# ProDoc_Rev1_21_2024-06-05.net
KiCad netlist of a schematic drawn in EasyEDA Pro
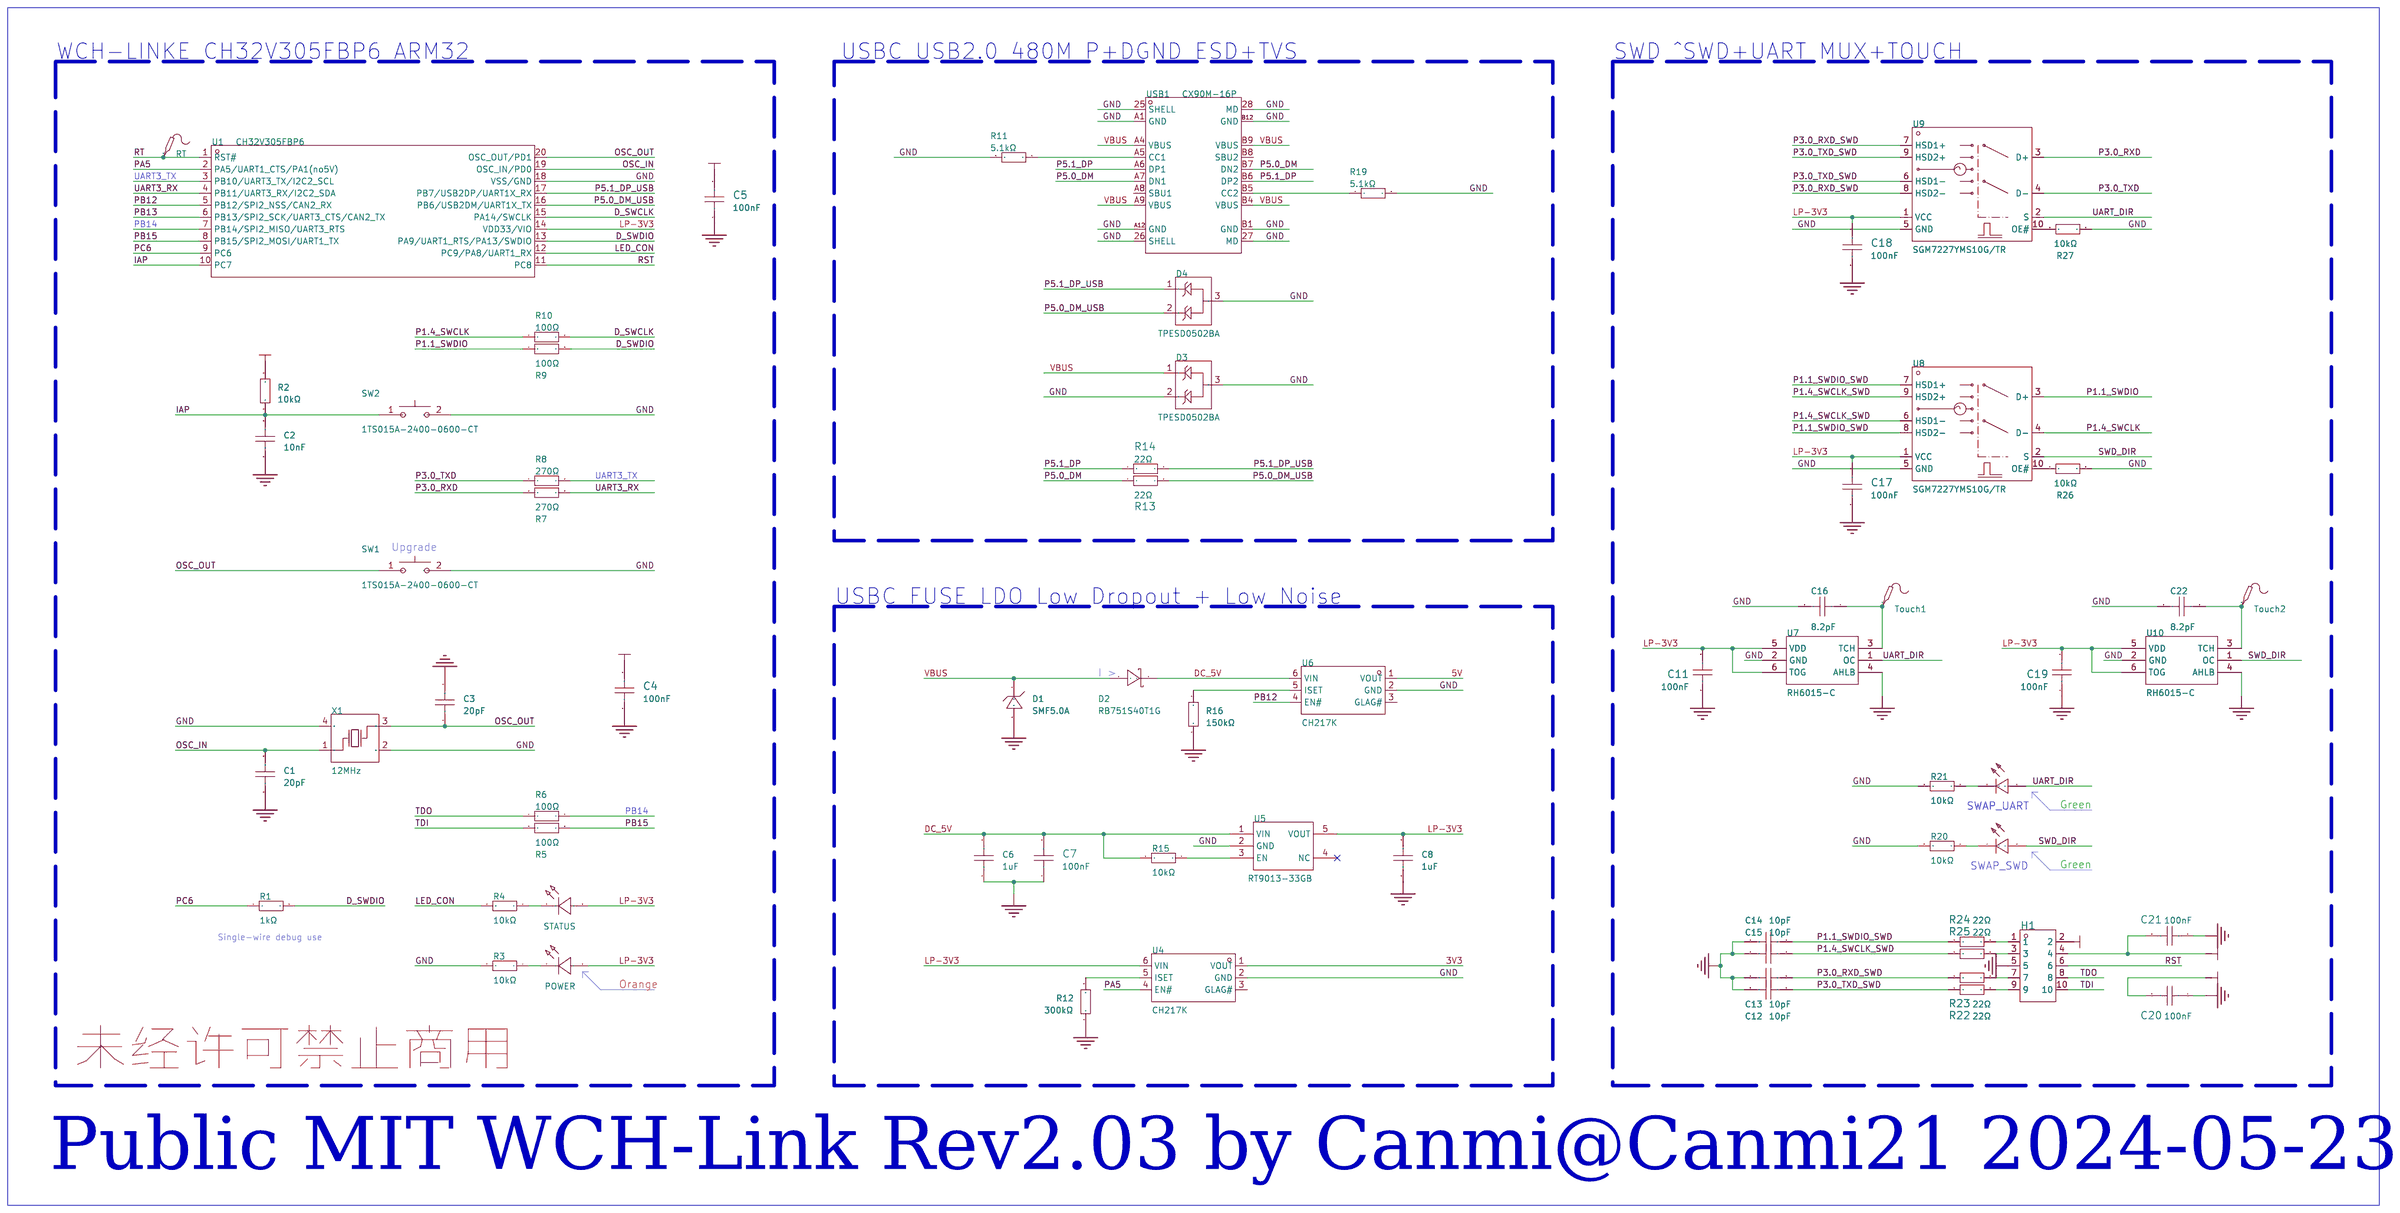
[diagram p0: schematic sheet]

(export (version "E")
  (design (tool "Eeschema 10.0.6"))
  (components
    (comp (ref "C1")
      (value "20pF")
      (footprint "easyedapro:C0402")
      (description "容值:20pF;精度:±5%;额定电压:50V;材质(温度系数):C0G;")
      (fields
        (field (name "Manufacturer Part") "GRM1555C1H200JA01D")
        (field (name "Manufacturer") "muRata(村田)")
      )
      (libsource (lib "easyedapro") (part "GRM1555C1H200JA01D"))
    )
    (comp (ref "C2")
      (value "10nF")
      (footprint "easyedapro:C0402")
      (description "容值:10nF;精度:±10%;额定电压:50V;材质(温度系数):X7R;")
      (fields
        (field (name "Manufacturer Part") "GCM155R71H103KA55D")
        (field (name "Manufacturer") "muRata(村田)")
      )
      (libsource (lib "easyedapro") (part "GCM155R71H103KA55D"))
    )
    (comp (ref "C3")
      (value "20pF")
      (footprint "easyedapro:C0402")
      (description "容值:20pF;精度:±5%;额定电压:50V;材质(温度系数):C0G;")
      (fields
        (field (name "Manufacturer Part") "GRM1555C1H200JA01D")
        (field (name "Manufacturer") "muRata(村田)")
      )
      (libsource (lib "easyedapro") (part "GRM1555C1H200JA01D"))
    )
    (comp (ref "C4")
      (value "100nF")
      (footprint "easyedapro:C0402")
      (description "容值:100nF;精度:±10%;额定电压:50V;材质(温度系数):X7R;")
      (fields
        (field (name "Manufacturer Part") "GRM155R71H104KE14D")
        (field (name "Manufacturer") "muRata(村田)")
      )
      (libsource (lib "easyedapro") (part "GRM155R71H104KE14D"))
    )
    (comp (ref "C5")
      (value "100nF")
      (footprint "easyedapro:C0402")
      (description "容值:100nF;精度:±10%;额定电压:50V;材质(温度系数):X7R;")
      (fields
        (field (name "Manufacturer Part") "GRM155R71H104KE14D")
        (field (name "Manufacturer") "muRata(村田)")
      )
      (libsource (lib "easyedapro") (part "GRM155R71H104KE14D"))
    )
    (comp (ref "C6")
      (value "1uF")
      (footprint "easyedapro:C0402")
      (description "容值:1uF;精度:±10%;额定电压:10V;材质(温度系数):X7R;")
      (fields
        (field (name "Manufacturer Part") "GRM155Z71A105KE01D")
        (field (name "Manufacturer") "muRata(村田)")
      )
      (libsource (lib "easyedapro") (part "GRM155Z71A105KE01D"))
    )
    (comp (ref "C7")
      (value "100nF")
      (footprint "easyedapro:C0402")
      (description "容值:100nF;精度:±10%;额定电压:50V;材质(温度系数):X7R;")
      (fields
        (field (name "Manufacturer Part") "GRM155R71H104KE14D")
        (field (name "Manufacturer") "muRata(村田)")
      )
      (libsource (lib "easyedapro") (part "GRM155R71H104KE14D"))
    )
    (comp (ref "C8")
      (value "1uF")
      (footprint "easyedapro:C0402")
      (description "容值:1uF;精度:±10%;额定电压:10V;材质(温度系数):X7R;")
      (fields
        (field (name "Manufacturer Part") "GRM155Z71A105KE01D")
        (field (name "Manufacturer") "muRata(村田)")
      )
      (libsource (lib "easyedapro") (part "GRM155Z71A105KE01D"))
    )
    (comp (ref "C11")
      (value "100nF")
      (footprint "easyedapro:C0402")
      (description "容值:100nF;精度:±10%;额定电压:50V;材质(温度系数):X7R;")
      (fields
        (field (name "Manufacturer Part") "GRM155R71H104KE14D")
        (field (name "Manufacturer") "muRata(村田)")
      )
      (libsource (lib "easyedapro") (part "GRM155R71H104KE14D"))
    )
    (comp (ref "C12")
      (value "10pF")
      (footprint "easyedapro:C0402")
      (description "容值:10pF;精度:±1%;额定电压:50V;材质(温度系数):C0G;")
      (fields
        (field (name "Manufacturer Part") "GRM1555C1H100FA01D")
        (field (name "Manufacturer") "muRata(村田)")
      )
      (libsource (lib "easyedapro") (part "GRM1555C1H100FA01D"))
    )
    (comp (ref "C13")
      (value "10pF")
      (footprint "easyedapro:C0402")
      (description "容值:10pF;精度:±1%;额定电压:50V;材质(温度系数):C0G;")
      (fields
        (field (name "Manufacturer Part") "GRM1555C1H100FA01D")
        (field (name "Manufacturer") "muRata(村田)")
      )
      (libsource (lib "easyedapro") (part "GRM1555C1H100FA01D"))
    )
    (comp (ref "C14")
      (value "10pF")
      (footprint "easyedapro:C0402")
      (description "容值:10pF;精度:±1%;额定电压:50V;材质(温度系数):C0G;")
      (fields
        (field (name "Manufacturer Part") "GRM1555C1H100FA01D")
        (field (name "Manufacturer") "muRata(村田)")
      )
      (libsource (lib "easyedapro") (part "GRM1555C1H100FA01D"))
    )
    (comp (ref "C15")
      (value "10pF")
      (footprint "easyedapro:C0402")
      (description "容值:10pF;精度:±1%;额定电压:50V;材质(温度系数):C0G;")
      (fields
        (field (name "Manufacturer Part") "GRM1555C1H100FA01D")
        (field (name "Manufacturer") "muRata(村田)")
      )
      (libsource (lib "easyedapro") (part "GRM1555C1H100FA01D"))
    )
    (comp (ref "C16")
      (value "8.2pF")
      (footprint "easyedapro:C0402")
      (description "容值:8.2pF;额定电压:50V;材质(温度系数):C0G;")
      (fields
        (field (name "Manufacturer Part") "GJM1555C1H8R2BB01D")
        (field (name "Manufacturer") "muRata(村田)")
      )
      (libsource (lib "easyedapro") (part "GJM1555C1H8R2BB01D"))
    )
    (comp (ref "C17")
      (value "100nF")
      (footprint "easyedapro:C0402")
      (description "容值:100nF;精度:±10%;额定电压:50V;材质(温度系数):X7R;")
      (fields
        (field (name "Manufacturer Part") "GRM155R71H104KE14D")
        (field (name "Manufacturer") "muRata(村田)")
      )
      (libsource (lib "easyedapro") (part "GRM155R71H104KE14D"))
    )
    (comp (ref "C18")
      (value "100nF")
      (footprint "easyedapro:C0402")
      (description "容值:100nF;精度:±10%;额定电压:50V;材质(温度系数):X7R;")
      (fields
        (field (name "Manufacturer Part") "GRM155R71H104KE14D")
        (field (name "Manufacturer") "muRata(村田)")
      )
      (libsource (lib "easyedapro") (part "GRM155R71H104KE14D"))
    )
    (comp (ref "C19")
      (value "100nF")
      (footprint "easyedapro:C0402")
      (description "容值:100nF;精度:±10%;额定电压:50V;材质(温度系数):X7R;")
      (fields
        (field (name "Manufacturer Part") "GRM155R71H104KE14D")
        (field (name "Manufacturer") "muRata(村田)")
      )
      (libsource (lib "easyedapro") (part "GRM155R71H104KE14D"))
    )
    (comp (ref "C20")
      (value "100nF")
      (footprint "easyedapro:C0402")
      (description "容值:100nF;精度:±10%;额定电压:50V;材质(温度系数):X7R;")
      (fields
        (field (name "Manufacturer Part") "GRM155R71H104KE14D")
        (field (name "Manufacturer") "muRata(村田)")
      )
      (libsource (lib "easyedapro") (part "GRM155R71H104KE14D"))
    )
    (comp (ref "C21")
      (value "100nF")
      (footprint "easyedapro:C0402")
      (description "容值:100nF;精度:±10%;额定电压:50V;材质(温度系数):X7R;")
      (fields
        (field (name "Manufacturer Part") "GRM155R71H104KE14D")
        (field (name "Manufacturer") "muRata(村田)")
      )
      (libsource (lib "easyedapro") (part "GRM155R71H104KE14D"))
    )
    (comp (ref "C22")
      (value "8.2pF")
      (footprint "easyedapro:C0402")
      (description "容值:8.2pF;额定电压:50V;材质(温度系数):C0G;")
      (fields
        (field (name "Manufacturer Part") "GJM1555C1H8R2BB01D")
        (field (name "Manufacturer") "muRata(村田)")
      )
      (libsource (lib "easyedapro") (part "GJM1555C1H8R2BB01D"))
    )
    (comp (ref "D1")
      (value "SMF5.0A")
      (footprint "easyedapro:SOD-123FL_L2.8-W1.7-LS3.6-RD")
      (description "反向截止电压(Vrwm):5V;最大钳位电压:9.2V;峰值脉冲电流(Ipp)@10/1000us:21.7A;峰值脉冲功率(Ppp)@10/1000us:200W;击穿电压:6.4V;")
      (fields (field (name "Manufacturer") "GOODWORK(固得沃克)"))
      (libsource (lib "easyedapro") (part "SMF5.0A_C2980403"))
    )
    (comp (ref "D2")
      (value "RB751S40T1G")
      (footprint "easyedapro:SOD-523_L1.2-W0.8-LS1.6-RD")
      (description "正向压降(Vf):370mV@1mA;直流反向耐压(Vr):40V;平均整流电流(Io):30mA;")
      (fields (field (name "Manufacturer") "onsemi(安森美)"))
      (libsource (lib "easyedapro") (part "RB751S40T1G"))
    )
    (comp (ref "D3")
      (value "TPESD0502BA")
      (footprint "easyedapro:SOT-523_L1.6-W0.8-P1.00-LS1.6-BR")
      (fields (field (name "Manufacturer") "TECH PUBLIC(台舟)"))
      (libsource (lib "easyedapro") (part "RCLAMP0502BA"))
    )
    (comp (ref "D4")
      (value "TPESD0502BA")
      (footprint "easyedapro:SOT-523_L1.6-W0.8-P1.00-LS1.6-BR")
      (fields (field (name "Manufacturer") "TECH PUBLIC(台舟)"))
      (libsource (lib "easyedapro") (part "RCLAMP0502BA"))
    )
    (comp (ref "H1")
      (value "X6521WV-2x05H-C60D30")
      (footprint "easyedapro:HDR-TH_10P-P2.54-V-M-R2-C5-S2.54")
      (fields (field (name "Manufacturer") "XKB Connectivity(中国星坤)"))
      (libsource (lib "easyedapro") (part "X6521WV-2×05H-C30D60"))
    )
    (comp (ref "R1")
      (value "1kΩ")
      (footprint "easyedapro:R0402")
      (description "电阻类型:厚膜电阻;阻值:1kΩ;精度:±1%;功率:62.5mW;")
      (fields
        (field (name "Manufacturer Part") "0402WGF1001TCE")
        (field (name "Manufacturer") "UNI-ROYAL(厚声)")
      )
      (libsource (lib "easyedapro") (part "0402WGF1001TCE"))
    )
    (comp (ref "R2")
      (value "10kΩ")
      (footprint "easyedapro:R0402")
      (description "电阻类型:厚膜电阻;阻值:10kΩ;精度:±1%;功率:62.5mW;")
      (fields
        (field (name "Manufacturer Part") "0402WGF1002TCE")
        (field (name "Manufacturer") "UNI-ROYAL(厚声)")
      )
      (libsource (lib "easyedapro") (part "0402WGF1002TCE"))
    )
    (comp (ref "R3")
      (value "10kΩ")
      (footprint "easyedapro:R0402")
      (description "电阻类型:厚膜电阻;阻值:10kΩ;精度:±1%;功率:62.5mW;")
      (fields
        (field (name "Manufacturer Part") "0402WGF1002TCE")
        (field (name "Manufacturer") "UNI-ROYAL(厚声)")
      )
      (libsource (lib "easyedapro") (part "0402WGF1002TCE"))
    )
    (comp (ref "R4")
      (value "10kΩ")
      (footprint "easyedapro:R0402")
      (description "电阻类型:厚膜电阻;阻值:10kΩ;精度:±1%;功率:62.5mW;")
      (fields
        (field (name "Manufacturer Part") "0402WGF1002TCE")
        (field (name "Manufacturer") "UNI-ROYAL(厚声)")
      )
      (libsource (lib "easyedapro") (part "0402WGF1002TCE"))
    )
    (comp (ref "R5")
      (value "100Ω")
      (footprint "easyedapro:R0402")
      (description "电阻类型:厚膜电阻;阻值:100Ω;精度:±1%;功率:62.5mW;最大工作电压:50V;温度系数:±200ppm/°C;")
      (fields
        (field (name "Manufacturer Part") "0402WGF1000TCE")
        (field (name "Manufacturer") "UNI-ROYAL(厚声)")
      )
      (libsource (lib "easyedapro") (part "0402WGF1000TCE"))
    )
    (comp (ref "R6")
      (value "100Ω")
      (footprint "easyedapro:R0402")
      (description "电阻类型:厚膜电阻;阻值:100Ω;精度:±1%;功率:62.5mW;最大工作电压:50V;温度系数:±200ppm/°C;")
      (fields
        (field (name "Manufacturer Part") "0402WGF1000TCE")
        (field (name "Manufacturer") "UNI-ROYAL(厚声)")
      )
      (libsource (lib "easyedapro") (part "0402WGF1000TCE"))
    )
    (comp (ref "R7")
      (value "270Ω")
      (footprint "easyedapro:R0402")
      (description "电阻类型:厚膜电阻;阻值:270Ω;精度:±1%;功率:62.5mW;最大工作电压:50V;温度系数:±100ppm/°C;")
      (fields
        (field (name "Manufacturer Part") "0402WGF2700TCE")
        (field (name "Manufacturer") "UNI-ROYAL(厚声)")
      )
      (libsource (lib "easyedapro") (part "0402WGF2700TCE"))
    )
    (comp (ref "R8")
      (value "270Ω")
      (footprint "easyedapro:R0402")
      (description "电阻类型:厚膜电阻;阻值:270Ω;精度:±1%;功率:62.5mW;最大工作电压:50V;温度系数:±100ppm/°C;")
      (fields
        (field (name "Manufacturer Part") "0402WGF2700TCE")
        (field (name "Manufacturer") "UNI-ROYAL(厚声)")
      )
      (libsource (lib "easyedapro") (part "0402WGF2700TCE"))
    )
    (comp (ref "R9")
      (value "100Ω")
      (footprint "easyedapro:R0402")
      (description "电阻类型:厚膜电阻;阻值:100Ω;精度:±1%;功率:62.5mW;最大工作电压:50V;温度系数:±200ppm/°C;")
      (fields
        (field (name "Manufacturer Part") "0402WGF1000TCE")
        (field (name "Manufacturer") "UNI-ROYAL(厚声)")
      )
      (libsource (lib "easyedapro") (part "0402WGF1000TCE"))
    )
    (comp (ref "R10")
      (value "100Ω")
      (footprint "easyedapro:R0402")
      (description "电阻类型:厚膜电阻;阻值:100Ω;精度:±1%;功率:62.5mW;最大工作电压:50V;温度系数:±200ppm/°C;")
      (fields
        (field (name "Manufacturer Part") "0402WGF1000TCE")
        (field (name "Manufacturer") "UNI-ROYAL(厚声)")
      )
      (libsource (lib "easyedapro") (part "0402WGF1000TCE"))
    )
    (comp (ref "R11")
      (value "5.1kΩ")
      (footprint "easyedapro:R0402")
      (description "电阻类型:厚膜电阻;阻值:5.1kΩ;精度:±1%;功率:62.5mW;")
      (fields
        (field (name "Manufacturer Part") "0402WGF5101TCE")
        (field (name "Manufacturer") "UNI-ROYAL(厚声)")
      )
      (libsource (lib "easyedapro") (part "0402WGF5101TCE"))
    )
    (comp (ref "R12")
      (value "300kΩ")
      (footprint "easyedapro:R0402")
      (description "电阻类型:厚膜电阻;阻值:300kΩ;精度:±1%;功率:62.5mW;最大工作电压:50V;温度系数:±100ppm/°C;")
      (fields
        (field (name "Manufacturer Part") "0402WGF3003TCE")
        (field (name "Manufacturer") "UNI-ROYAL(厚声)")
      )
      (libsource (lib "easyedapro") (part "0402WGF3003TCE"))
    )
    (comp (ref "R13")
      (value "22Ω")
      (footprint "easyedapro:R0402")
      (description "电阻类型:厚膜电阻;阻值:22Ω;精度:±1%;功率:62.5mW;温度系数:±100ppm/°C;")
      (fields
        (field (name "Manufacturer Part") "0402WGF220JTCE")
        (field (name "Manufacturer") "UNI-ROYAL(厚声)")
      )
      (libsource (lib "easyedapro") (part "0402WGF220JTCE"))
    )
    (comp (ref "R14")
      (value "22Ω")
      (footprint "easyedapro:R0402")
      (description "电阻类型:厚膜电阻;阻值:22Ω;精度:±1%;功率:62.5mW;温度系数:±100ppm/°C;")
      (fields
        (field (name "Manufacturer Part") "0402WGF220JTCE")
        (field (name "Manufacturer") "UNI-ROYAL(厚声)")
      )
      (libsource (lib "easyedapro") (part "0402WGF220JTCE"))
    )
    (comp (ref "R15")
      (value "10kΩ")
      (footprint "easyedapro:R0402")
      (description "电阻类型:厚膜电阻;阻值:10kΩ;精度:±1%;功率:62.5mW;")
      (fields
        (field (name "Manufacturer Part") "0402WGF1002TCE")
        (field (name "Manufacturer") "UNI-ROYAL(厚声)")
      )
      (libsource (lib "easyedapro") (part "0402WGF1002TCE"))
    )
    (comp (ref "R16")
      (value "150kΩ")
      (footprint "easyedapro:R0402")
      (description "电阻类型:厚膜电阻;阻值:150kΩ;精度:±1%;功率:62.5mW;最大工作电压:50V;温度系数:±100ppm/°C;")
      (fields
        (field (name "Manufacturer Part") "0402WGF1503TCE")
        (field (name "Manufacturer") "UNI-ROYAL(厚声)")
      )
      (libsource (lib "easyedapro") (part "0402WGF1503TCE"))
    )
    (comp (ref "R19")
      (value "5.1kΩ")
      (footprint "easyedapro:R0402")
      (description "电阻类型:厚膜电阻;阻值:5.1kΩ;精度:±1%;功率:62.5mW;")
      (fields
        (field (name "Manufacturer Part") "0402WGF5101TCE")
        (field (name "Manufacturer") "UNI-ROYAL(厚声)")
      )
      (libsource (lib "easyedapro") (part "0402WGF5101TCE"))
    )
    (comp (ref "R20")
      (value "10kΩ")
      (footprint "easyedapro:R0402")
      (description "电阻类型:厚膜电阻;阻值:10kΩ;精度:±1%;功率:62.5mW;")
      (fields
        (field (name "Manufacturer Part") "0402WGF1002TCE")
        (field (name "Manufacturer") "UNI-ROYAL(厚声)")
      )
      (libsource (lib "easyedapro") (part "0402WGF1002TCE"))
    )
    (comp (ref "R21")
      (value "10kΩ")
      (footprint "easyedapro:R0402")
      (description "电阻类型:厚膜电阻;阻值:10kΩ;精度:±1%;功率:62.5mW;")
      (fields
        (field (name "Manufacturer Part") "0402WGF1002TCE")
        (field (name "Manufacturer") "UNI-ROYAL(厚声)")
      )
      (libsource (lib "easyedapro") (part "0402WGF1002TCE"))
    )
    (comp (ref "R22")
      (value "22Ω")
      (footprint "easyedapro:R0402")
      (description "电阻类型:厚膜电阻;阻值:22Ω;精度:±1%;功率:62.5mW;温度系数:±100ppm/°C;")
      (fields
        (field (name "Manufacturer Part") "0402WGF220JTCE")
        (field (name "Manufacturer") "UNI-ROYAL(厚声)")
      )
      (libsource (lib "easyedapro") (part "0402WGF220JTCE"))
    )
    (comp (ref "R23")
      (value "22Ω")
      (footprint "easyedapro:R0402")
      (description "电阻类型:厚膜电阻;阻值:22Ω;精度:±1%;功率:62.5mW;温度系数:±100ppm/°C;")
      (fields
        (field (name "Manufacturer Part") "0402WGF220JTCE")
        (field (name "Manufacturer") "UNI-ROYAL(厚声)")
      )
      (libsource (lib "easyedapro") (part "0402WGF220JTCE"))
    )
    (comp (ref "R24")
      (value "22Ω")
      (footprint "easyedapro:R0402")
      (description "电阻类型:厚膜电阻;阻值:22Ω;精度:±1%;功率:62.5mW;温度系数:±100ppm/°C;")
      (fields
        (field (name "Manufacturer Part") "0402WGF220JTCE")
        (field (name "Manufacturer") "UNI-ROYAL(厚声)")
      )
      (libsource (lib "easyedapro") (part "0402WGF220JTCE"))
    )
    (comp (ref "R25")
      (value "22Ω")
      (footprint "easyedapro:R0402")
      (description "电阻类型:厚膜电阻;阻值:22Ω;精度:±1%;功率:62.5mW;温度系数:±100ppm/°C;")
      (fields
        (field (name "Manufacturer Part") "0402WGF220JTCE")
        (field (name "Manufacturer") "UNI-ROYAL(厚声)")
      )
      (libsource (lib "easyedapro") (part "0402WGF220JTCE"))
    )
    (comp (ref "R26")
      (value "10kΩ")
      (footprint "easyedapro:R0402")
      (description "电阻类型:厚膜电阻;阻值:10kΩ;精度:±1%;功率:62.5mW;")
      (fields
        (field (name "Manufacturer Part") "0402WGF1002TCE")
        (field (name "Manufacturer") "UNI-ROYAL(厚声)")
      )
      (libsource (lib "easyedapro") (part "0402WGF1002TCE"))
    )
    (comp (ref "R27")
      (value "10kΩ")
      (footprint "easyedapro:R0402")
      (description "电阻类型:厚膜电阻;阻值:10kΩ;精度:±1%;功率:62.5mW;")
      (fields
        (field (name "Manufacturer Part") "0402WGF1002TCE")
        (field (name "Manufacturer") "UNI-ROYAL(厚声)")
      )
      (libsource (lib "easyedapro") (part "0402WGF1002TCE"))
    )
    (comp (ref "RT")
      (value "~")
      (footprint "easyedapro:Test-Point-0.5mm")
      (description "Test Point 测试点")
      (libsource (lib "easyedapro") (part "Test-Point"))
    )
    (comp (ref "SW1")
      (value "1TS015A-2400-0600-CT")
      (footprint "easyedapro:SW-SMD_L3.0-W2.0-LS3.5")
      (fields (field (name "Manufacturer") "HYP(鸿源精密)"))
      (libsource (lib "easyedapro") (part "1TS015A-2400-0600"))
    )
    (comp (ref "SW2")
      (value "1TS015A-2400-0600-CT")
      (footprint "easyedapro:SW-SMD_L3.0-W2.0-LS3.5")
      (fields (field (name "Manufacturer") "HYP(鸿源精密)"))
      (libsource (lib "easyedapro") (part "1TS015A-2400-0600"))
    )
    (comp (ref "SWAP_SWD")
      (value "NCD0603R1")
      (footprint "easyedapro:LED0603-RD_RED")
      (description "发光颜色:红灯;")
      (fields (field (name "Manufacturer") "国星光电"))
      (libsource (lib "easyedapro") (part "FC-DA1608HRK-620D"))
    )
    (comp (ref "SWAP_UART")
      (value "NCD0603R1")
      (footprint "easyedapro:LED0603-RD_RED")
      (description "发光颜色:红灯;")
      (fields (field (name "Manufacturer") "国星光电"))
      (libsource (lib "easyedapro") (part "FC-DA1608HRK-620D"))
    )
    (comp (ref "Touch1")
      (value "~")
      (footprint "easyedapro:Test-Point-0.5mm")
      (description "Test Point 测试点")
      (libsource (lib "easyedapro") (part "Test-Point"))
    )
    (comp (ref "Touch2")
      (value "~")
      (footprint "easyedapro:Test-Point-0.5mm")
      (description "Test Point 测试点")
      (libsource (lib "easyedapro") (part "Test-Point"))
    )
    (comp (ref "U1")
      (value "CH32V305FBP6")
      (footprint "easyedapro:TSSOP-20_L6.5-W4.4-P0.65-LS6.4-BL")
      (fields (field (name "Manufacturer") "WCH(南京沁恒)"))
      (libsource (lib "easyedapro") (part "CH32V305FBP6"))
    )
    (comp (ref "U2")
      (value "POWER")
      (footprint "easyedapro:LED0402-RD_ORANGE")
      (description "发光颜色:橙色;功率:55mW;正向电流:25mA;主波长:600nm;透镜颜色:无色透明透镜;色温:-;发光角度:120°;载带方式:正贴;工作温度:-30°C~+85°C;")
      (fields (field (name "Manufacturer") "XINGLIGHT(成兴光)"))
      (libsource (lib "easyedapro") (part "XL-1005UOC"))
    )
    (comp (ref "U3")
      (value "STATUS")
      (footprint "easyedapro:LED0402-RD_BLUE")
      (description "发光颜色:冰蓝色;功率:80mW;正向电流:25mA;主波长:-;二极管配置:-;透镜颜色:绿色透镜;色温:-;发光角度:120°;载带方式:正贴;工作温度:-30°C~+85°C;")
      (fields (field (name "Manufacturer") "XINGLIGHT(成兴光)"))
      (libsource (lib "easyedapro") (part "XL-1005BGWC"))
    )
    (comp (ref "U4")
      (value "CH217K")
      (footprint "easyedapro:SOT-23-6_L2.9-W1.6-P0.95-LS2.8-BL")
      (libsource (lib "easyedapro") (part "CH217K"))
    )
    (comp (ref "U5")
      (value "RT9013-33GB")
      (footprint "easyedapro:SOT-23-5_L3.0-W1.7-P0.95-LS2.8-BL")
      (description "输出类型:固定;最大输入电压:5.5V;输出电压:3.3V;最大输出电流:500mA;电源纹波抑制比(PSRR):50dB@(10kHz);输出极性:正极;")
      (fields (field (name "Manufacturer") "RICHTEK(立锜)"))
      (libsource (lib "easyedapro") (part "RT9013-33GB"))
    )
    (comp (ref "U6")
      (value "CH217K")
      (footprint "easyedapro:SOT-23-6_L2.9-W1.6-P0.95-LS2.8-BL")
      (libsource (lib "easyedapro") (part "CH217K"))
    )
    (comp (ref "U7")
      (value "RH6015-C")
      (footprint "easyedapro:SOT-23-6_L2.9-W1.6-P0.95-LS2.8-BR")
      (description "通道数:1;芯片功能:电容式触 摸感应;是否自锁:否;工作电压:2.3V~5.5V;工作电流:5uA;工作温度:-20°C~85°C;")
      (fields (field (name "Manufacturer") "RONGHE(融和)"))
      (libsource (lib "easyedapro") (part "RH6015-C"))
    )
    (comp (ref "U8")
      (value "SGM7227YMS10G/TR")
      (footprint "easyedapro:MSOP-10_L3.0-W3.0-P0.50-LS5.0-BL")
      (description "开关电路:-;多路复用器/解复用器电路:-;导通电阻（最大值）:-;开关电压（最大值）:-;")
      (fields (field (name "Manufacturer") "SGMICRO(圣邦微)"))
      (libsource (lib "easyedapro") (part "SGM7227YMS10G/TR"))
    )
    (comp (ref "U9")
      (value "SGM7227YMS10G/TR")
      (footprint "easyedapro:MSOP-10_L3.0-W3.0-P0.50-LS5.0-BL")
      (description "开关电路:-;多路复用器/解复用器电路:-;导通电阻（最大值）:-;开关电压（最大值）:-;")
      (fields (field (name "Manufacturer") "SGMICRO(圣邦微)"))
      (libsource (lib "easyedapro") (part "SGM7227YMS10G/TR"))
    )
    (comp (ref "U10")
      (value "RH6015-C")
      (footprint "easyedapro:SOT-23-6_L2.9-W1.6-P0.95-LS2.8-BR")
      (description "通道数:1;芯片功能:电容式触 摸感应;是否自锁:否;工作电压:2.3V~5.5V;工作电流:5uA;工作温度:-20°C~85°C;")
      (fields (field (name "Manufacturer") "RONGHE(融和)"))
      (libsource (lib "easyedapro") (part "RH6015-C"))
    )
    (comp (ref "USB1")
      (value "CX90M-16P")
      (footprint "easyedapro:USB-C-SMD_CX90M-16P")
      (description "连接器类型:Type-C;标准:USB 2.0;公母:母;端口数量:1;触点数量:16P;安装方式:沉板;额定电流 - 电源:-;工作温度范围:-30°C~+85°C;")
      (fields (field (name "Manufacturer") "HRS(广濑)"))
      (libsource (lib "easyedapro") (part "CX90M-16P"))
    )
    (comp (ref "X1")
      (value "12MHz")
      (footprint "easyedapro:OSC-SMD_4P-L3.2-W2.5-BL")
      (description "晶振类型:贴片晶振;频率:12MHz;常温频差:±10ppm;外接负载电容:20pF;频率稳定度(全温):±20ppm;")
      (fields (field (name "Manufacturer Part") "X322512MSB4SI") (field (name "Manufacturer") "YXC(扬兴晶振)"))
      (libsource (lib "easyedapro") (part "X322512MSB4SI"))
    )
  )
  (nets
    (net (code "1") (name "/DC_5V") (class "Default")
      (node (ref "C6") (pin "2") (pinfunction "2_2") (pintype "unspecified"))
      (node (ref "C7") (pin "2") (pinfunction "2_2") (pintype "input"))
      (node (ref "D2") (pin "1") (pinfunction "K_1") (pintype "unspecified"))
      (node (ref "R15") (pin "2") (pinfunction "2_2") (pintype "input"))
      (node (ref "U5") (pin "1") (pinfunction "VIN_1") (pintype "unspecified"))
      (node (ref "U6") (pin "6") (pinfunction "VIN_6") (pintype "unspecified"))
    )
    (net (code "2") (name "/D_SWCLK") (class "Default")
      (node (ref "R10") (pin "2") (pinfunction "2_2") (pintype "input"))
      (node (ref "U1") (pin "15") (pinfunction "PA14/SWCLK_15") (pintype "unspecified"))
    )
    (net (code "3") (name "/D_SWDIO") (class "Default")
      (node (ref "R1") (pin "2") (pinfunction "2_2") (pintype "input"))
      (node (ref "R9") (pin "2") (pinfunction "2_2") (pintype "input"))
      (node (ref "U1") (pin "13") (pinfunction "PA9/UART1_RTS/PA13/SWDIO_13") (pintype "unspecified"))
    )
    (net (code "4") (name "/IAP") (class "Default")
      (node (ref "C2") (pin "2") (pinfunction "2_2") (pintype "unspecified"))
      (node (ref "R2") (pin "2") (pinfunction "2_2") (pintype "input"))
      (node (ref "SW2") (pin "1") (pinfunction "1_1") (pintype "input"))
      (node (ref "U1") (pin "10") (pinfunction "PC7_10") (pintype "unspecified"))
    )
    (net (code "5") (name "/LED_CON") (class "Default")
      (node (ref "R4") (pin "2") (pinfunction "2_2") (pintype "input"))
      (node (ref "U1") (pin "12") (pinfunction "PC9/PA8/UART1_RX_12") (pintype "unspecified"))
    )
    (net (code "6") (name "/OSC_IN") (class "Default")
      (node (ref "C1") (pin "2") (pinfunction "2_2") (pintype "unspecified"))
      (node (ref "U1") (pin "19") (pinfunction "OSC_IN/PD0_19") (pintype "unspecified"))
      (node (ref "X1") (pin "1") (pinfunction "OSC1_1") (pintype "unspecified"))
    )
    (net (code "7") (name "/OSC_OUT") (class "Default")
      (node (ref "C3") (pin "1") (pinfunction "1_1") (pintype "unspecified"))
      (node (ref "SW1") (pin "1") (pinfunction "1_1") (pintype "input"))
      (node (ref "U1") (pin "20") (pinfunction "OSC_OUT/PD1_20") (pintype "unspecified"))
      (node (ref "X1") (pin "3") (pinfunction "OSC2_3") (pintype "unspecified"))
    )
    (net (code "8") (name "/P1.1_SWDIO") (class "Default")
      (node (ref "R9") (pin "1") (pinfunction "1_1") (pintype "input"))
      (node (ref "U8") (pin "3") (pinfunction "D+_3") (pintype "input"))
    )
    (net (code "9") (name "/P1.1_SWDIO_SWD") (class "Default")
      (node (ref "C15") (pin "1") (pinfunction "1_1") (pintype "input"))
      (node (ref "R25") (pin "1") (pinfunction "1_1") (pintype "input"))
      (node (ref "U8") (pin "7") (pinfunction "HSD1+_7") (pintype "input"))
      (node (ref "U8") (pin "8") (pinfunction "HSD2-_8") (pintype "input"))
    )
    (net (code "10") (name "/P1.4_SWCLK") (class "Default")
      (node (ref "R10") (pin "1") (pinfunction "1_1") (pintype "input"))
      (node (ref "U8") (pin "4") (pinfunction "D-_4") (pintype "input"))
    )
    (net (code "11") (name "/P1.4_SWCLK_SWD") (class "Default")
      (node (ref "C14") (pin "1") (pinfunction "1_1") (pintype "input"))
      (node (ref "R24") (pin "1") (pinfunction "1_1") (pintype "input"))
      (node (ref "U8") (pin "6") (pinfunction "HSD1-_6") (pintype "input"))
      (node (ref "U8") (pin "9") (pinfunction "HSD2+_9") (pintype "input"))
    )
    (net (code "12") (name "/P3.0_RXD") (class "Default")
      (node (ref "R7") (pin "1") (pinfunction "1_1") (pintype "input"))
      (node (ref "U9") (pin "3") (pinfunction "D+_3") (pintype "input"))
    )
    (net (code "13") (name "/P3.0_RXD_SWD") (class "Default")
      (node (ref "C13") (pin "1") (pinfunction "1_1") (pintype "input"))
      (node (ref "R23") (pin "1") (pinfunction "1_1") (pintype "input"))
      (node (ref "U9") (pin "7") (pinfunction "HSD1+_7") (pintype "input"))
      (node (ref "U9") (pin "8") (pinfunction "HSD2-_8") (pintype "input"))
    )
    (net (code "14") (name "/P3.0_TXD") (class "Default")
      (node (ref "R8") (pin "1") (pinfunction "1_1") (pintype "input"))
      (node (ref "U9") (pin "4") (pinfunction "D-_4") (pintype "input"))
    )
    (net (code "15") (name "/P3.0_TXD_SWD") (class "Default")
      (node (ref "C12") (pin "1") (pinfunction "1_1") (pintype "input"))
      (node (ref "R22") (pin "1") (pinfunction "1_1") (pintype "input"))
      (node (ref "U9") (pin "6") (pinfunction "HSD1-_6") (pintype "input"))
      (node (ref "U9") (pin "9") (pinfunction "HSD2+_9") (pintype "input"))
    )
    (net (code "16") (name "/P5.0_DM") (class "Default")
      (node (ref "R13") (pin "1") (pinfunction "1_1") (pintype "input"))
      (node (ref "USB1") (pin "A7") (pinfunction "DN1_A7") (pintype "unspecified"))
      (node (ref "USB1") (pin "B7") (pinfunction "DN2_B7") (pintype "unspecified"))
    )
    (net (code "17") (name "/P5.0_DM_USB") (class "Default")
      (node (ref "D4") (pin "2") (pinfunction "2_2") (pintype "unspecified"))
      (node (ref "R13") (pin "2") (pinfunction "2_2") (pintype "input"))
      (node (ref "U1") (pin "16") (pinfunction "PB6/USB2DM/UART1X_TX_16") (pintype "unspecified"))
    )
    (net (code "18") (name "/P5.1_DP") (class "Default")
      (node (ref "R14") (pin "1") (pinfunction "1_1") (pintype "input"))
      (node (ref "USB1") (pin "A6") (pinfunction "DP1_A6") (pintype "unspecified"))
      (node (ref "USB1") (pin "B6") (pinfunction "DP2_B6") (pintype "unspecified"))
    )
    (net (code "19") (name "/P5.1_DP_USB") (class "Default")
      (node (ref "D4") (pin "1") (pinfunction "1_1") (pintype "unspecified"))
      (node (ref "R14") (pin "2") (pinfunction "2_2") (pintype "input"))
      (node (ref "U1") (pin "17") (pinfunction "PB7/USB2DP/UART1X_RX_17") (pintype "unspecified"))
    )
    (net (code "20") (name "/PA5") (class "Default")
      (node (ref "U1") (pin "2") (pinfunction "PA5/UART1_CTS/PA1(no5V)_2") (pintype "unspecified"))
      (node (ref "U4") (pin "4") (pinfunction "EN#_4") (pintype "unspecified"))
    )
    (net (code "21") (name "/PB12") (class "Default")
      (node (ref "U1") (pin "5") (pinfunction "PB12/SPI2_NSS/CAN2_RX_5") (pintype "unspecified"))
      (node (ref "U6") (pin "4") (pinfunction "EN#_4") (pintype "unspecified"))
    )
    (net (code "22") (name "/PB13") (class "Default")
      (node (ref "U1") (pin "6") (pinfunction "PB13/SPI2_SCK/UART3_CTS/CAN2_TX_6") (pintype "unspecified"))
    )
    (net (code "23") (name "/PB14") (class "Default")
      (node (ref "R6") (pin "2") (pinfunction "2_2") (pintype "input"))
      (node (ref "U1") (pin "7") (pinfunction "PB14/SPI2_MISO/UART3_RTS_7") (pintype "unspecified"))
    )
    (net (code "24") (name "/PB15") (class "Default")
      (node (ref "R5") (pin "2") (pinfunction "2_2") (pintype "input"))
      (node (ref "U1") (pin "8") (pinfunction "PB15/SPI2_MOSI/UART1_TX_8") (pintype "unspecified"))
    )
    (net (code "25") (name "/PC6") (class "Default")
      (node (ref "R1") (pin "1") (pinfunction "1_1") (pintype "input"))
      (node (ref "U1") (pin "9") (pinfunction "PC6_9") (pintype "unspecified"))
    )
    (net (code "26") (name "/RST") (class "Default")
      (node (ref "H1") (pin "6") (pinfunction "6_6") (pintype "input"))
      (node (ref "U1") (pin "11") (pinfunction "PC8_11") (pintype "unspecified"))
    )
    (net (code "27") (name "/RT") (class "Default")
      (node (ref "RT") (pin "1") (pinfunction "1_1") (pintype "input"))
      (node (ref "U1") (pin "1") (pinfunction "RST#_1") (pintype "unspecified"))
    )
    (net (code "28") (name "/SWD_DIR") (class "Default")
      (node (ref "SWAP_SWD") (pin "2") (pinfunction "A_2") (pintype "input"))
      (node (ref "U10") (pin "1") (pinfunction "OC_1") (pintype "input"))
      (node (ref "U8") (pin "2") (pinfunction "S_2") (pintype "input"))
    )
    (net (code "29") (name "/TDI") (class "Default")
      (node (ref "H1") (pin "10") (pinfunction "10_10") (pintype "input"))
      (node (ref "R5") (pin "1") (pinfunction "1_1") (pintype "input"))
    )
    (net (code "30") (name "/TDO") (class "Default")
      (node (ref "H1") (pin "8") (pinfunction "8_8") (pintype "input"))
      (node (ref "R6") (pin "1") (pinfunction "1_1") (pintype "input"))
    )
    (net (code "31") (name "/UART3_RX") (class "Default")
      (node (ref "R7") (pin "2") (pinfunction "2_2") (pintype "input"))
      (node (ref "U1") (pin "4") (pinfunction "PB11/UART3_RX/I2C2_SDA_4") (pintype "unspecified"))
    )
    (net (code "32") (name "/UART3_TX") (class "Default")
      (node (ref "R8") (pin "2") (pinfunction "2_2") (pintype "input"))
      (node (ref "U1") (pin "3") (pinfunction "PB10/UART3_TX/I2C2_SCL_3") (pintype "unspecified"))
    )
    (net (code "33") (name "/UART_DIR") (class "Default")
      (node (ref "SWAP_UART") (pin "2") (pinfunction "A_2") (pintype "input"))
      (node (ref "U7") (pin "1") (pinfunction "OC_1") (pintype "input"))
      (node (ref "U9") (pin "2") (pinfunction "S_2") (pintype "input"))
    )
    (net (code "34") (name "/VBUS") (class "Default")
      (node (ref "D1") (pin "1") (pinfunction "1_1") (pintype "unspecified"))
      (node (ref "D2") (pin "2") (pinfunction "A_2") (pintype "unspecified"))
      (node (ref "D3") (pin "1") (pinfunction "1_1") (pintype "unspecified"))
      (node (ref "USB1") (pin "A4") (pinfunction "VBUS_A4") (pintype "unspecified"))
      (node (ref "USB1") (pin "A9") (pinfunction "VBUS_A9") (pintype "unspecified"))
      (node (ref "USB1") (pin "B4") (pinfunction "VBUS_B4") (pintype "unspecified"))
      (node (ref "USB1") (pin "B9") (pinfunction "VBUS_B9") (pintype "unspecified"))
    )
    (net (code "35") (name "3V3") (class "Default")
      (node (ref "C21") (pin "2") (pinfunction "2_2") (pintype "input"))
      (node (ref "H1") (pin "4") (pinfunction "4_4") (pintype "input"))
      (node (ref "U4") (pin "1") (pinfunction "VOUT_1") (pintype "unspecified"))
    )
    (net (code "36") (name "5V") (class "Default")
      (node (ref "C20") (pin "2") (pinfunction "2_2") (pintype "input"))
      (node (ref "H1") (pin "2") (pinfunction "2_2") (pintype "input"))
      (node (ref "U6") (pin "1") (pinfunction "VOUT_1") (pintype "unspecified"))
    )
    (net (code "37") (name "GND") (class "Default")
      (node (ref "C1") (pin "1") (pinfunction "1_1") (pintype "unspecified"))
      (node (ref "C11") (pin "1") (pinfunction "1_1") (pintype "input"))
      (node (ref "C12") (pin "2") (pinfunction "2_2") (pintype "input"))
      (node (ref "C13") (pin "2") (pinfunction "2_2") (pintype "input"))
      (node (ref "C14") (pin "2") (pinfunction "2_2") (pintype "input"))
      (node (ref "C15") (pin "2") (pinfunction "2_2") (pintype "input"))
      (node (ref "C16") (pin "2") (pinfunction "2_2") (pintype "unspecified"))
      (node (ref "C17") (pin "1") (pinfunction "1_1") (pintype "input"))
      (node (ref "C18") (pin "1") (pinfunction "1_1") (pintype "input"))
      (node (ref "C19") (pin "1") (pinfunction "1_1") (pintype "input"))
      (node (ref "C2") (pin "1") (pinfunction "1_1") (pintype "unspecified"))
      (node (ref "C20") (pin "1") (pinfunction "1_1") (pintype "input"))
      (node (ref "C21") (pin "1") (pinfunction "1_1") (pintype "input"))
      (node (ref "C22") (pin "2") (pinfunction "2_2") (pintype "unspecified"))
      (node (ref "C3") (pin "2") (pinfunction "2_2") (pintype "unspecified"))
      (node (ref "C4") (pin "1") (pinfunction "1_1") (pintype "input"))
      (node (ref "C5") (pin "1") (pinfunction "1_1") (pintype "input"))
      (node (ref "C6") (pin "1") (pinfunction "1_1") (pintype "unspecified"))
      (node (ref "C7") (pin "1") (pinfunction "1_1") (pintype "input"))
      (node (ref "C8") (pin "1") (pinfunction "1_1") (pintype "unspecified"))
      (node (ref "D1") (pin "2") (pinfunction "2_2") (pintype "unspecified"))
      (node (ref "D3") (pin "2") (pinfunction "2_2") (pintype "unspecified"))
      (node (ref "D3") (pin "3") (pinfunction "3_3") (pintype "unspecified"))
      (node (ref "D4") (pin "3") (pinfunction "3_3") (pintype "unspecified"))
      (node (ref "H1") (pin "5") (pinfunction "5_5") (pintype "input"))
      (node (ref "R11") (pin "2") (pinfunction "2_2") (pintype "input"))
      (node (ref "R12") (pin "1") (pinfunction "1_1") (pintype "input"))
      (node (ref "R16") (pin "1") (pinfunction "1_1") (pintype "input"))
      (node (ref "R19") (pin "2") (pinfunction "2_2") (pintype "input"))
      (node (ref "R20") (pin "2") (pinfunction "2_2") (pintype "input"))
      (node (ref "R21") (pin "2") (pinfunction "2_2") (pintype "input"))
      (node (ref "R26") (pin "2") (pinfunction "2_2") (pintype "input"))
      (node (ref "R27") (pin "2") (pinfunction "2_2") (pintype "input"))
      (node (ref "R3") (pin "2") (pinfunction "2_2") (pintype "input"))
      (node (ref "SW1") (pin "2") (pinfunction "2_2") (pintype "input"))
      (node (ref "SW2") (pin "2") (pinfunction "2_2") (pintype "input"))
      (node (ref "U1") (pin "18") (pinfunction "VSS/GND_18") (pintype "unspecified"))
      (node (ref "U10") (pin "2") (pinfunction "GND_2") (pintype "input"))
      (node (ref "U10") (pin "4") (pinfunction "AHLB_4") (pintype "input"))
      (node (ref "U4") (pin "2") (pinfunction "GND_2") (pintype "unspecified"))
      (node (ref "U5") (pin "2") (pinfunction "GND_2") (pintype "unspecified"))
      (node (ref "U6") (pin "2") (pinfunction "GND_2") (pintype "unspecified"))
      (node (ref "U7") (pin "2") (pinfunction "GND_2") (pintype "input"))
      (node (ref "U7") (pin "4") (pinfunction "AHLB_4") (pintype "input"))
      (node (ref "U8") (pin "5") (pinfunction "GND_5") (pintype "input"))
      (node (ref "U9") (pin "5") (pinfunction "GND_5") (pintype "input"))
      (node (ref "USB1") (pin "25") (pinfunction "SHELL_25") (pintype "unspecified"))
      (node (ref "USB1") (pin "26") (pinfunction "SHELL_26") (pintype "unspecified"))
      (node (ref "USB1") (pin "27") (pinfunction "MD_27") (pintype "unspecified"))
      (node (ref "USB1") (pin "28") (pinfunction "MD_28") (pintype "unspecified"))
      (node (ref "USB1") (pin "A1") (pinfunction "GND_A1") (pintype "unspecified"))
      (node (ref "USB1") (pin "A12") (pinfunction "GND_A12") (pintype "unspecified"))
      (node (ref "USB1") (pin "B1") (pinfunction "GND_B1") (pintype "unspecified"))
      (node (ref "USB1") (pin "B12") (pinfunction "GND_B12") (pintype "unspecified"))
      (node (ref "X1") (pin "2") (pinfunction "GND_2") (pintype "unspecified"))
      (node (ref "X1") (pin "4") (pinfunction "GND_4") (pintype "unspecified"))
    )
    (net (code "38") (name "LP-3V3") (class "Default")
      (node (ref "C11") (pin "2") (pinfunction "2_2") (pintype "input"))
      (node (ref "C17") (pin "2") (pinfunction "2_2") (pintype "input"))
      (node (ref "C18") (pin "2") (pinfunction "2_2") (pintype "input"))
      (node (ref "C19") (pin "2") (pinfunction "2_2") (pintype "input"))
      (node (ref "C4") (pin "2") (pinfunction "2_2") (pintype "input"))
      (node (ref "C5") (pin "2") (pinfunction "2_2") (pintype "input"))
      (node (ref "C8") (pin "2") (pinfunction "2_2") (pintype "unspecified"))
      (node (ref "R2") (pin "1") (pinfunction "1_1") (pintype "input"))
      (node (ref "U1") (pin "14") (pinfunction "VDD33/VIO_14") (pintype "unspecified"))
      (node (ref "U10") (pin "5") (pinfunction "VDD_5") (pintype "input"))
      (node (ref "U10") (pin "6") (pinfunction "TOG_6") (pintype "input"))
      (node (ref "U2") (pin "2") (pinfunction "A_2") (pintype "unspecified"))
      (node (ref "U3") (pin "2") (pinfunction "A_2") (pintype "unspecified"))
      (node (ref "U4") (pin "6") (pinfunction "VIN_6") (pintype "unspecified"))
      (node (ref "U5") (pin "5") (pinfunction "VOUT_5") (pintype "unspecified"))
      (node (ref "U7") (pin "5") (pinfunction "VDD_5") (pintype "input"))
      (node (ref "U7") (pin "6") (pinfunction "TOG_6") (pintype "input"))
      (node (ref "U8") (pin "1") (pinfunction "VCC_1") (pintype "input"))
      (node (ref "U9") (pin "1") (pinfunction "VCC_1") (pintype "input"))
    )
    (net (code "39") (name "Net-(H1-Pad1)") (class "Default")
      (node (ref "H1") (pin "1") (pinfunction "1_1") (pintype "input"))
      (node (ref "R25") (pin "2") (pinfunction "2_2") (pintype "input"))
    )
    (net (code "40") (name "Net-(H1-Pad3)") (class "Default")
      (node (ref "H1") (pin "3") (pinfunction "3_3") (pintype "input"))
      (node (ref "R24") (pin "2") (pinfunction "2_2") (pintype "input"))
    )
    (net (code "41") (name "Net-(H1-Pad7)") (class "Default")
      (node (ref "H1") (pin "7") (pinfunction "7_7") (pintype "input"))
      (node (ref "R23") (pin "2") (pinfunction "2_2") (pintype "input"))
    )
    (net (code "42") (name "Net-(H1-Pad9)") (class "Default")
      (node (ref "H1") (pin "9") (pinfunction "9_9") (pintype "input"))
      (node (ref "R22") (pin "2") (pinfunction "2_2") (pintype "input"))
    )
    (net (code "43") (name "Net-(SWAP_SWD-K)") (class "Default")
      (node (ref "R20") (pin "1") (pinfunction "1_1") (pintype "input"))
      (node (ref "SWAP_SWD") (pin "1") (pinfunction "K_1") (pintype "input"))
    )
    (net (code "44") (name "Net-(SWAP_UART-K)") (class "Default")
      (node (ref "R21") (pin "1") (pinfunction "1_1") (pintype "input"))
      (node (ref "SWAP_UART") (pin "1") (pinfunction "K_1") (pintype "input"))
    )
    (net (code "45") (name "Net-(U2-K)") (class "Default")
      (node (ref "R3") (pin "1") (pinfunction "1_1") (pintype "input"))
      (node (ref "U2") (pin "1") (pinfunction "K_1") (pintype "unspecified"))
    )
    (net (code "46") (name "Net-(U3-K)") (class "Default")
      (node (ref "R4") (pin "1") (pinfunction "1_1") (pintype "input"))
      (node (ref "U3") (pin "1") (pinfunction "K_1") (pintype "unspecified"))
    )
    (net (code "47") (name "Net-(U4-ISET)") (class "Default")
      (node (ref "R12") (pin "2") (pinfunction "2_2") (pintype "input"))
      (node (ref "U4") (pin "5") (pinfunction "ISET_5") (pintype "unspecified"))
    )
    (net (code "48") (name "Net-(U5-EN)") (class "Default")
      (node (ref "R15") (pin "1") (pinfunction "1_1") (pintype "input"))
      (node (ref "U5") (pin "3") (pinfunction "EN_3") (pintype "unspecified"))
    )
    (net (code "49") (name "Net-(U6-ISET)") (class "Default")
      (node (ref "R16") (pin "2") (pinfunction "2_2") (pintype "input"))
      (node (ref "U6") (pin "5") (pinfunction "ISET_5") (pintype "unspecified"))
    )
    (net (code "50") (name "Net-(U7-TCH)") (class "Default")
      (node (ref "C16") (pin "1") (pinfunction "1_1") (pintype "unspecified"))
      (node (ref "Touch1") (pin "1") (pinfunction "1_1") (pintype "input"))
      (node (ref "U7") (pin "3") (pinfunction "TCH_3") (pintype "input"))
    )
    (net (code "51") (name "Net-(U8-OE#)") (class "Default")
      (node (ref "R26") (pin "1") (pinfunction "1_1") (pintype "input"))
      (node (ref "U8") (pin "10") (pinfunction "OE#_10") (pintype "input"))
    )
    (net (code "52") (name "Net-(U9-OE#)") (class "Default")
      (node (ref "R27") (pin "1") (pinfunction "1_1") (pintype "input"))
      (node (ref "U9") (pin "10") (pinfunction "OE#_10") (pintype "input"))
    )
    (net (code "53") (name "Net-(U10-TCH)") (class "Default")
      (node (ref "C22") (pin "1") (pinfunction "1_1") (pintype "unspecified"))
      (node (ref "Touch2") (pin "1") (pinfunction "1_1") (pintype "input"))
      (node (ref "U10") (pin "3") (pinfunction "TCH_3") (pintype "input"))
    )
    (net (code "54") (name "Net-(USB1-CC1)") (class "Default")
      (node (ref "R11") (pin "1") (pinfunction "1_1") (pintype "input"))
      (node (ref "USB1") (pin "A5") (pinfunction "CC1_A5") (pintype "unspecified"))
    )
    (net (code "55") (name "Net-(USB1-CC2)") (class "Default")
      (node (ref "R19") (pin "1") (pinfunction "1_1") (pintype "input"))
      (node (ref "USB1") (pin "B5") (pinfunction "CC2_B5") (pintype "unspecified"))
    )
    (net (code "56") (name "unconnected-(U4-GLAG#-Pad3)") (class "Default")
      (node (ref "U4") (pin "3") (pinfunction "GLAG#_3") (pintype "unspecified"))
    )
    (net (code "57") (name "unconnected-(U5-NC-Pad4)") (class "Default")
      (node (ref "U5") (pin "4") (pinfunction "NC_4") (pintype "unspecified+no_connect"))
    )
    (net (code "58") (name "unconnected-(U6-GLAG#-Pad3)") (class "Default")
      (node (ref "U6") (pin "3") (pinfunction "GLAG#_3") (pintype "unspecified"))
    )
    (net (code "59") (name "unconnected-(USB1-SBU1-PadA8)") (class "Default")
      (node (ref "USB1") (pin "A8") (pinfunction "SBU1_A8") (pintype "unspecified"))
    )
    (net (code "60") (name "unconnected-(USB1-SBU2-PadB8)") (class "Default")
      (node (ref "USB1") (pin "B8") (pinfunction "SBU2_B8") (pintype "unspecified"))
    )
  )
)
